# OpenBLC_TPS62152.net
KiCad netlist of a schematic drawn in Altium Designer
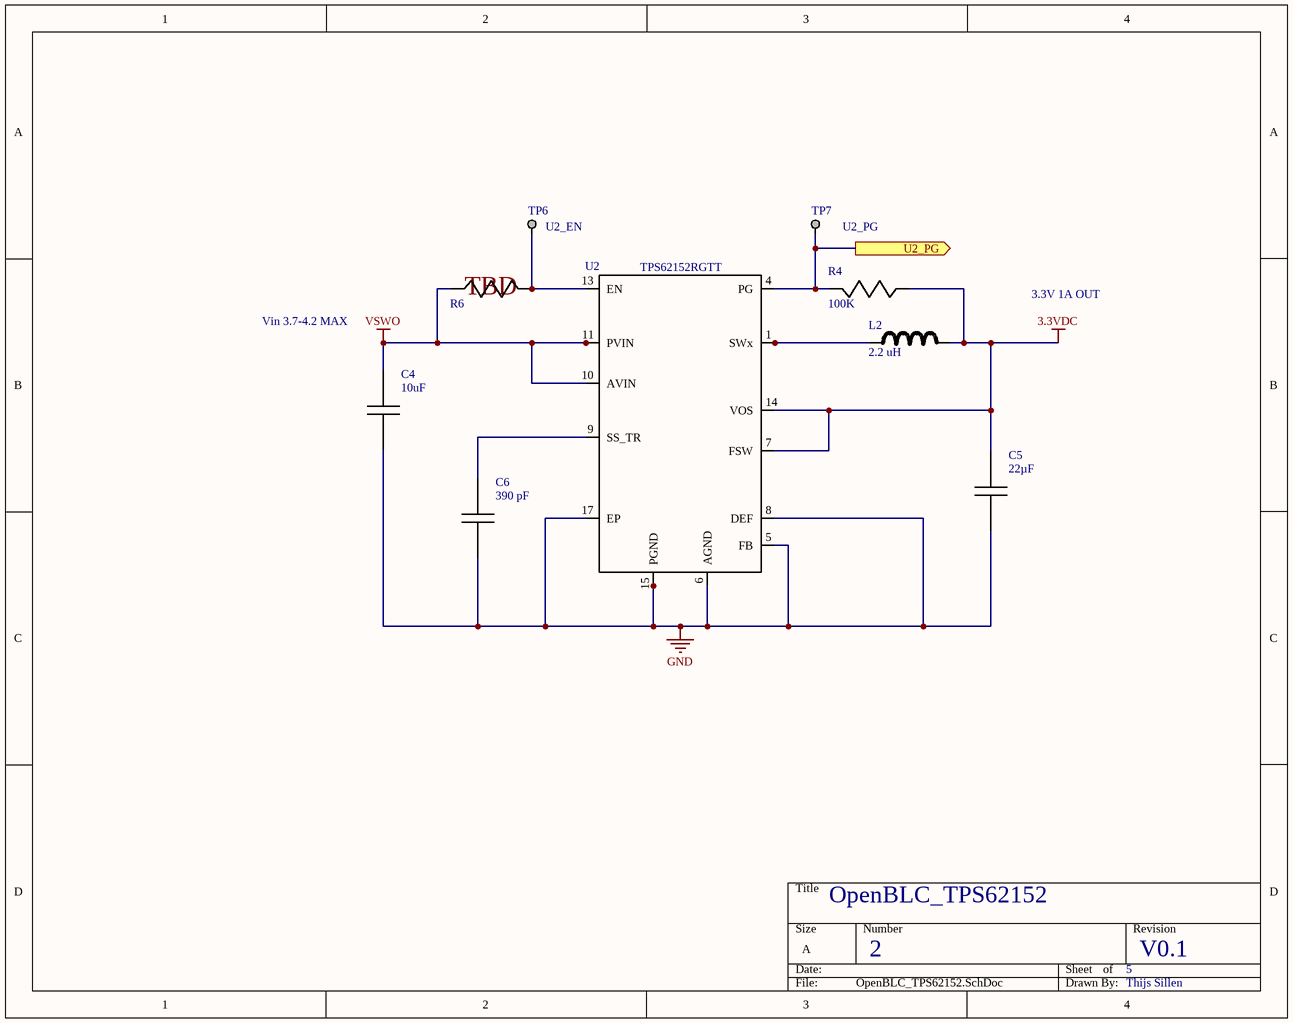
[diagram p0: OpenBLC_TPS62152.SchDoc]

(export (version "E")
  (design (tool "Eeschema 10.0.6"))
  (components
    (comp (ref "C4")
      (value "GRM21BR61A106KE19L")
      (footprint "0805_CAP")
      (description "MURATA - GRM21BR61A106KE19L - CAPACITOR, CERA, 10UF, 10%, 10V, 10%, SMD")
      (fields (field (name "MANUFACTURER") "MURATA") (field (name "CAPACITANCE") "10uF"))
      (libsource (lib "Schlib1") (part "GRM21BR61A106KE19L"))
    )
    (comp (ref "C5")
      (value "C2012X5R0J226M125AC")
      (footprint "0805_CAP")
      (description "CAP CER 22UF 6.3V 20% X5R 0805")
      (fields
        (field (name "MANUFACTURER") "TDK Corporation")
        (field (name "TOLERANCE") "±20%")
        (field (name "CAPACITANCE") "22µF")
      )
      (libsource (lib "Schlib1") (part "C2012X5R0J226M125AC"))
    )
    (comp (ref "C6")
      (value "GRM033R71C391KA01D")
      (footprint "0603_CAP")
      (description "Meerlaagse keramische condensatoren MLCC - SMD/SMT 390pF 16 volts 10%")
      (fields (field (name "MANUFACTURER") "Murata Electronics") (field (name "CAPACITEIT") "390 pF"))
      (libsource (lib "Schlib1") (part "GRM033R71C391KA01D"))
    )
    (comp (ref "L2")
      (value "SDR0403-2R2ML")
      (footprint "SDR0403")
      (description "Vaste smoorspoelen 2.2uH 20% SMD 0403")
      (fields (field (name "MANUFACTURER") "Bourns") (field (name "INDUCTANTIE") "2.2 uH"))
      (libsource (lib "Schlib1") (part "SDR0403-2R2ML"))
    )
    (comp (ref "R4")
      (value "CRCW0402100KFKEDHP")
      (footprint "0402_RES")
      (description "VISHAY DRALORIC - CRCW0402100KFKEDHP - RESISTOR, POWER, 100K, 0.125W, 1%")
      (fields (field (name "MANUFACTURER") "VISHAY DRALORIC") (field (name "RESISTANCE") "100K"))
      (libsource (lib "Schlib1") (part "CRCW0402100KFKEDHP"))
    )
    (comp (ref "R6") (value "0805_RES") (footprint "0805_RES") (libsource (lib "Schlib1") (part "0805_RES")))
    (comp (ref "TP6")
      (value "U2_EN")
      (footprint "Via_TP")
      (description "TESTPOINT SCOPE GRABBER")
      (fields
        (field (name "MANUFACTURER PART NUMBER") "5010")
        (field (name "MANUFACTURER") "Keystone Electronics")
      )
      (libsource (lib "vh_altium_library") (part "TESTPOINT"))
    )
    (comp (ref "TP7")
      (value "U2_PG")
      (footprint "Via_TP")
      (description "TESTPOINT SCOPE GRABBER")
      (fields
        (field (name "MANUFACTURER PART NUMBER") "5010")
        (field (name "MANUFACTURER") "Keystone Electronics")
      )
      (libsource (lib "vh_altium_library") (part "TESTPOINT"))
    )
    (comp (ref "U2")
      (value "TPS62152RGTT")
      (footprint "TPS62152RGTR")
      (fields (field (name "MANUFACTURER") "Texas Instruments"))
      (libsource (lib "Schlib1") (part "TPS62152RGTT"))
    )
  )
  (nets
    (net (code "1") (name "/U2_PG") (class "Default")
      (node (ref "R4") (pin "1") (pinfunction "1_1") (pintype "passive"))
      (node (ref "TP7") (pin "1") (pinfunction "1_1") (pintype "passive"))
      (node (ref "U2") (pin "4") (pinfunction "PG_4") (pintype "passive"))
    )
    (net (code "2") (name "3.3VDC") (class "Default")
      (node (ref "C5") (pin "1") (pinfunction "1_1") (pintype "passive"))
      (node (ref "L2") (pin "1") (pinfunction "1_1") (pintype "passive"))
      (node (ref "R4") (pin "2") (pinfunction "2_2") (pintype "passive"))
      (node (ref "U2") (pin "14") (pinfunction "VOS_14") (pintype "passive"))
      (node (ref "U2") (pin "7") (pinfunction "FSW_7") (pintype "passive"))
    )
    (net (code "3") (name "GND") (class "Default")
      (node (ref "C4") (pin "2") (pinfunction "2_2") (pintype "passive"))
      (node (ref "C5") (pin "2") (pinfunction "2_2") (pintype "passive"))
      (node (ref "C6") (pin "2") (pinfunction "2_2") (pintype "passive"))
      (node (ref "U2") (pin "15") (pinfunction "PGND_15") (pintype "passive"))
      (node (ref "U2") (pin "16") (pinfunction "PGND_16") (pintype "passive"))
      (node (ref "U2") (pin "17") (pinfunction "EP_17") (pintype "passive"))
      (node (ref "U2") (pin "5") (pinfunction "FB_5") (pintype "passive"))
      (node (ref "U2") (pin "6") (pinfunction "AGND_6") (pintype "passive"))
      (node (ref "U2") (pin "8") (pinfunction "DEF_8") (pintype "passive"))
    )
    (net (code "4") (name "Net-(U2-EN)") (class "Default")
      (node (ref "R6") (pin "1") (pinfunction "1_1") (pintype "passive"))
      (node (ref "TP6") (pin "1") (pinfunction "1_1") (pintype "passive"))
      (node (ref "U2") (pin "13") (pinfunction "EN_13") (pintype "passive"))
    )
    (net (code "5") (name "Net-(U2-SS_TR)") (class "Default")
      (node (ref "C6") (pin "1") (pinfunction "1_1") (pintype "passive"))
      (node (ref "U2") (pin "9") (pinfunction "SS_TR_9") (pintype "passive"))
    )
    (net (code "6") (name "Net-(U2-SWx)") (class "Default")
      (node (ref "L2") (pin "2") (pinfunction "2_2") (pintype "passive"))
      (node (ref "U2") (pin "1") (pinfunction "SWx_1") (pintype "passive"))
      (node (ref "U2") (pin "2") (pinfunction "SW_2") (pintype "passive"))
      (node (ref "U2") (pin "3") (pinfunction "SW_3") (pintype "passive"))
    )
    (net (code "7") (name "VSWO") (class "Default")
      (node (ref "C4") (pin "1") (pinfunction "1_1") (pintype "passive"))
      (node (ref "R6") (pin "2") (pinfunction "2_2") (pintype "passive"))
      (node (ref "U2") (pin "10") (pinfunction "AVIN_10") (pintype "passive"))
      (node (ref "U2") (pin "11") (pinfunction "PVIN_11") (pintype "passive"))
      (node (ref "U2") (pin "12") (pinfunction "PVIN_12") (pintype "passive"))
    )
  )
)
